# ShutdownLoop.net
KiCad netlist of a schematic drawn in Altium Designer
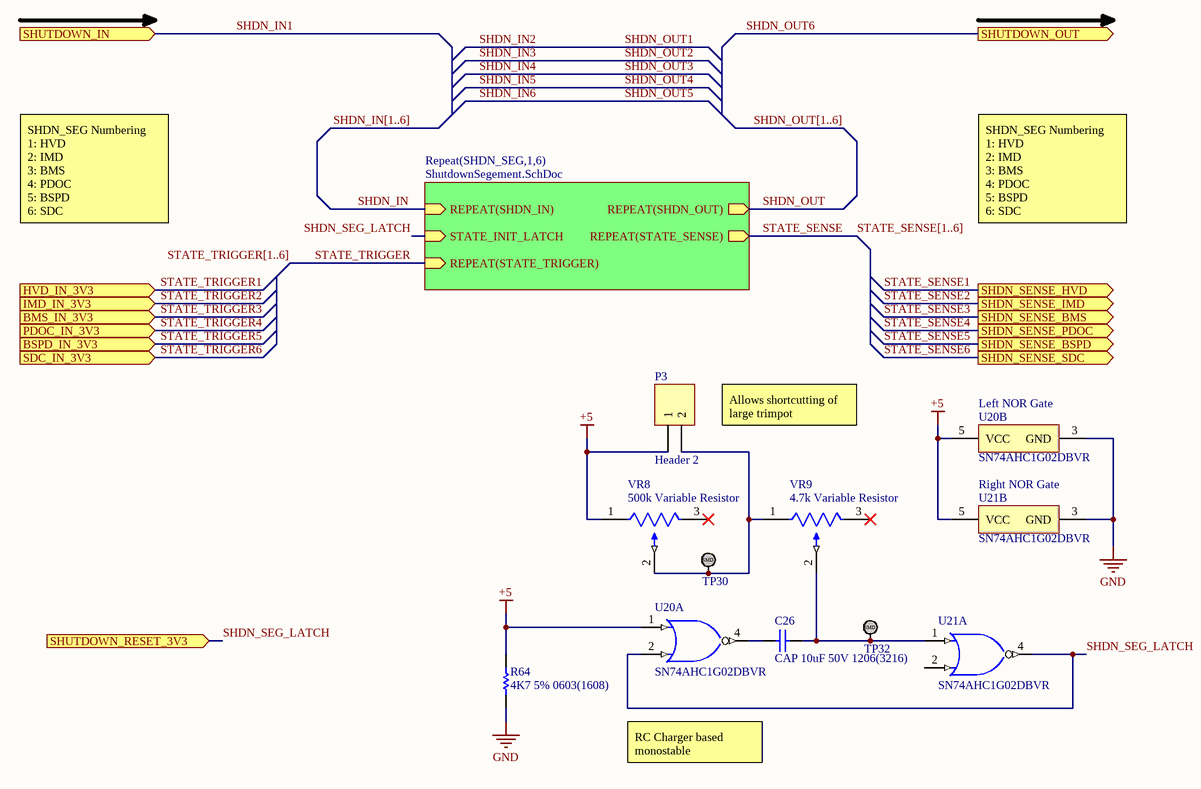
[diagram p0: ShutdownLoop.SchDoc]

(export (version "E")
  (design (tool "Eeschema 10.0.6"))
  (components
    (comp (ref "C26")
      (value "CAP 10uF 50V 1206(3216)")
      (footprint "CAPC1206(3216)190_M")
      (description "CAP 10uF 50V ±10% 1206 (3216 Metric) Thickness 1.9mm SMD")
      (fields (field (name "TOLERANCE") "Â±10%"))
      (libsource (lib "Altium Content Vault") (part "CAP"))
    )
    (comp (ref "P3")
      (value "Header 2")
      (footprint "HDR1X2")
      (description "Header, 2-Pin")
      (fields (field (name "PUBLISHER") "Altium Limited"))
      (libsource (lib "Miscellaneous Connectors") (part "Header 2"))
    )
    (comp (ref "R64")
      (value "4K7 5% 0603(1608)")
      (footprint "RESC0603(1608)_N")
      (description "4K7 0.1W 5% 0603 (1608 Metric)  SMD")
      (fields (field (name "TOLERANCE") "5 %") (field (name "POWER") "0.1 W"))
      (libsource (lib "Altium Content Vault") (part "RES"))
    )
    (comp (ref "TP30")
      (value "TestPoint_SMD")
      (footprint "TestPointSMD")
      (libsource (lib "StandardTest") (part "TestPoint_SMD"))
    )
    (comp (ref "TP32")
      (value "TestPoint_SMD")
      (footprint "TestPointSMD")
      (libsource (lib "StandardTest") (part "TestPoint_SMD"))
    )
    (comp (ref "U20")
      (value "SN74AHC1G02DBVR")
      (footprint "DBV0005A_L")
      (description "Single 2-Input Positive-NOR Gate, DBV0005A, LARGE T&R")
      (fields
        (field (name "MANUFACTURER") "Texas Instruments")
        (field (name "GENERIC PART NUMBER") "SN74AHC1G02")
      )
      (libsource (lib "Altium Content Vault") (part "TI-SN74XXX1X02-5"))
    )
    (comp (ref "U21")
      (value "SN74AHC1G02DBVR")
      (footprint "DBV0005A_L")
      (description "Single 2-Input Positive-NOR Gate, DBV0005A, LARGE T&R")
      (fields
        (field (name "MANUFACTURER") "Texas Instruments")
        (field (name "GENERIC PART NUMBER") "SN74AHC1G02")
      )
      (libsource (lib "Altium Content Vault") (part "TI-SN74XXX1X02-5"))
    )
    (comp (ref "VR8")
      (value "500k Variable Resistor")
      (footprint "VG039NCHXTB472")
      (description "500K ±25% ±250 ppm/°C SMD Variable Resistors RoHS ¦ VG039NCHXTB504")
      (libsource (lib "QUTMS_PotentiometerLibrary") (part "500k Variable Resistor"))
    )
    (comp (ref "VR9")
      (value "4.7k Variable Resistor")
      (footprint "VG039NCHXTB472")
      (description "4k7 ±25% ±250 ppm/°C SMD Variable Resistors RoHS ¦ VG039NCHXTB472")
      (libsource (lib "QUTMS_PotentiometerLibrary") (part "4.7k Variable Resistor"))
    )
  )
  (nets
    (net (code "1") (name "+5") (class "Default")
      (node (ref "P3") (pin "1") (pinfunction "1_1") (pintype "passive"))
      (node (ref "R64") (pin "2") (pinfunction "2_2") (pintype "passive"))
      (node (ref "U20") (pin "1") (pinfunction "A_1") (pintype "input"))
      (node (ref "U20") (pin "5") (pinfunction "VCC_5") (pintype "power_in"))
      (node (ref "U21") (pin "5") (pinfunction "VCC_5") (pintype "power_in"))
      (node (ref "VR8") (pin "1") (pinfunction "48_1") (pintype "passive"))
    )
    (net (code "13") (name "/SHDN_SEG_LATCH") (class "Default")
      (node (ref "U20") (pin "2") (pinfunction "B_2") (pintype "input"))
      (node (ref "U21") (pin "4") (pinfunction "Y_4") (pintype "output"))
    )
    (net (code "30") (name "GND") (class "Default")
      (node (ref "R64") (pin "1") (pinfunction "1_1") (pintype "passive"))
      (node (ref "U20") (pin "3") (pinfunction "GND_3") (pintype "power_in"))
      (node (ref "U21") (pin "3") (pinfunction "GND_3") (pintype "power_in"))
    )
    (net (code "31") (name "Net-(U20A-Y)") (class "Default")
      (node (ref "C26") (pin "2") (pinfunction "2_2") (pintype "passive"))
      (node (ref "U20") (pin "4") (pinfunction "Y_4") (pintype "output"))
    )
    (net (code "32") (name "Net-(U21A-A)") (class "Default")
      (node (ref "C26") (pin "1") (pinfunction "1_1") (pintype "passive"))
      (node (ref "TP32") (pin "1") (pinfunction "1_1") (pintype "passive"))
      (node (ref "U21") (pin "1") (pinfunction "A_1") (pintype "input"))
      (node (ref "VR9") (pin "2") (pinfunction "50_2") (pintype "output"))
    )
    (net (code "33") (name "Net-(VR8-50)") (class "Default")
      (node (ref "P3") (pin "2") (pinfunction "2_2") (pintype "passive"))
      (node (ref "TP30") (pin "1") (pinfunction "1_1") (pintype "passive"))
      (node (ref "VR8") (pin "2") (pinfunction "50_2") (pintype "output"))
      (node (ref "VR9") (pin "1") (pinfunction "48_1") (pintype "passive"))
    )
    (net (code "34") (name "unconnected-(U21A-B-Pad2)") (class "Default")
      (node (ref "U21") (pin "2") (pinfunction "B_2") (pintype "input"))
    )
    (net (code "35") (name "unconnected-(VR8-49-Pad3)") (class "Default")
      (node (ref "VR8") (pin "3") (pinfunction "49_3") (pintype "passive+no_connect"))
    )
    (net (code "36") (name "unconnected-(VR9-49-Pad3)") (class "Default")
      (node (ref "VR9") (pin "3") (pinfunction "49_3") (pintype "passive+no_connect"))
    )
  )
)
